# Consola_ESP32_V2.net
KiCad netlist of a schematic drawn in Altium Designer
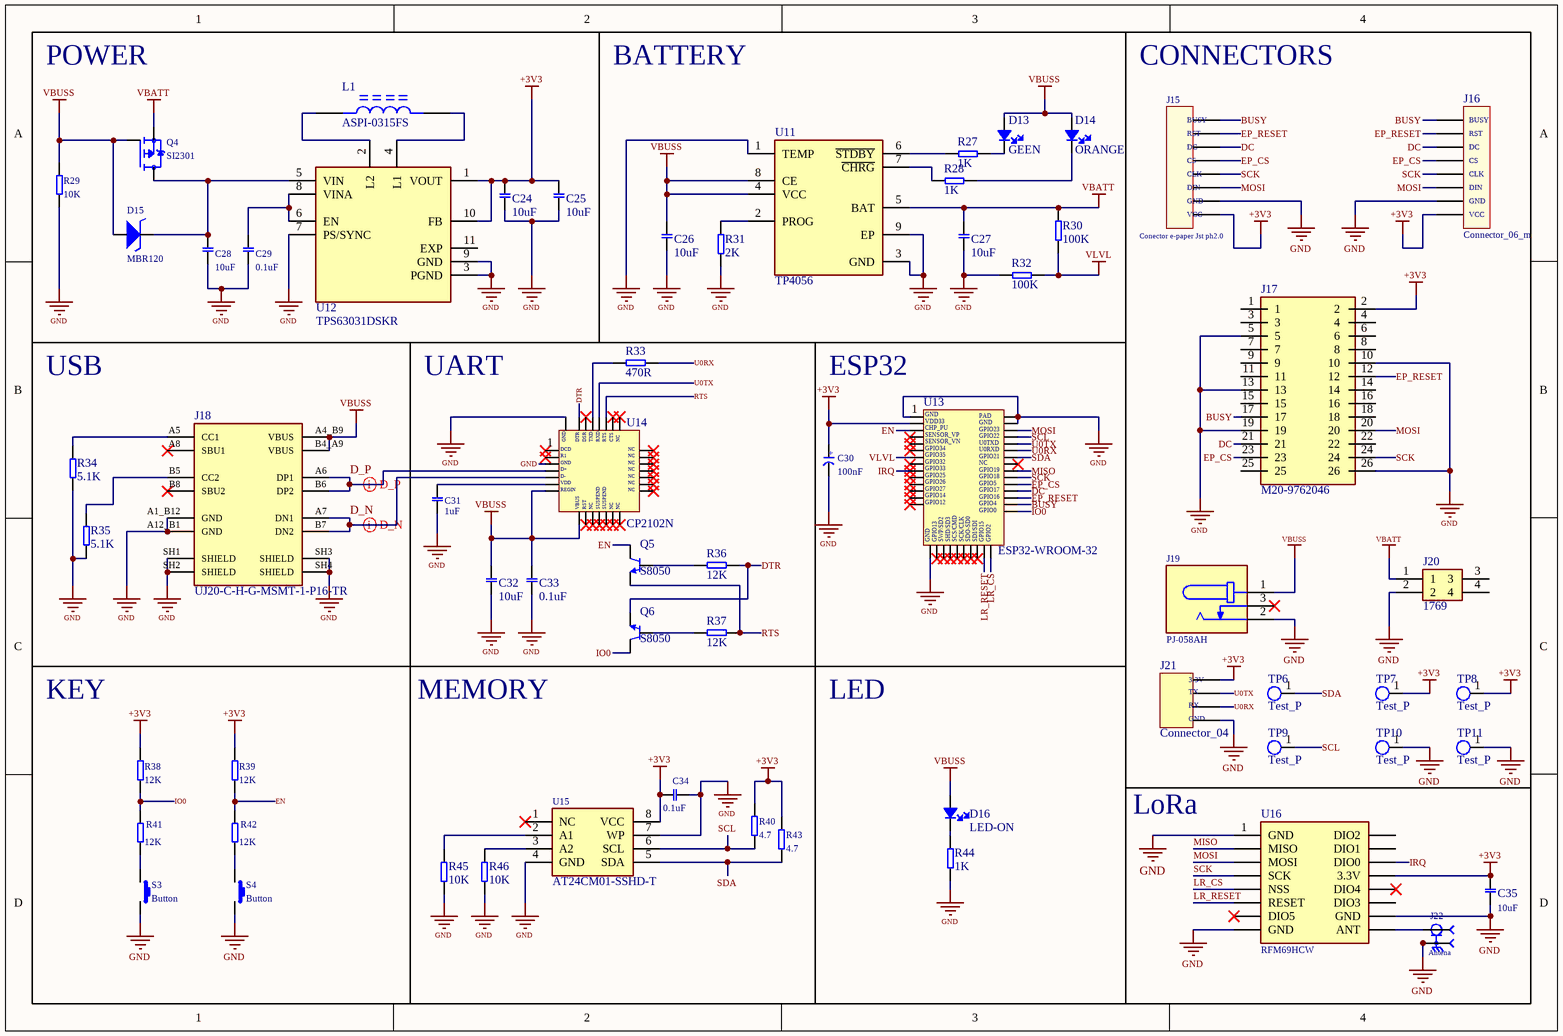
[diagram p0: Consola_ESP32_V2.SchDoc]

(export (version "E")
  (design (tool "Eeschema 10.0.6"))
  (components
    (comp (ref "C24")
      (value "10uF")
      (footprint "CAPCP1608_0603")
      (description "Capacitor_10uF_0603")
      (libsource (lib "Estacion_Meteorologica_Final") (part "C0603X100J1GACAUTO"))
    )
    (comp (ref "C25")
      (value "10uF")
      (footprint "CAPCP1608_0603")
      (description "Capacitor_10uF_0603")
      (libsource (lib "Estacion_Meteorologica_Final") (part "C0603X100J1GACAUTO"))
    )
    (comp (ref "C26")
      (value "10uF")
      (footprint "CAPCP1608_0603")
      (description "Capacitor_10uF_0603")
      (libsource (lib "Estacion_Meteorologica_Final") (part "C0603X100J1GACAUTO"))
    )
    (comp (ref "C27")
      (value "10uF")
      (footprint "CAPCP1608_0603")
      (description "Capacitor_10uF_0603")
      (libsource (lib "Estacion_Meteorologica_Final") (part "C0603X100J1GACAUTO"))
    )
    (comp (ref "C28")
      (value "10uF")
      (footprint "CAPCP1608_0603")
      (description "Capacitor_10uF_0603")
      (libsource (lib "Estacion_Meteorologica_Final") (part "C0603X100J1GACAUTO"))
    )
    (comp (ref "C29")
      (value "0.1uF")
      (footprint "CAPCP1608_0603")
      (description "Capacitor_0.1uF_0603")
      (libsource (lib "Estacion_Meteorologica_Final") (part "06035C104K4T4A"))
    )
    (comp (ref "C30")
      (value "100nF")
      (footprint "CAPC_1206")
      (description "Capacitor_100uF_1206")
      (libsource (lib "Estacion_Meteorologica_Final") (part "TAJD107K016RNJ"))
    )
    (comp (ref "C31")
      (value "1uF")
      (footprint "CAPCP1608_0603")
      (description "Capacitor_1uF_0603")
      (libsource (lib "Estacion_Meteorologica_Final") (part "C0603X105J4RACTU"))
    )
    (comp (ref "C32")
      (value "10uF")
      (footprint "CAPCP1608_0603")
      (description "Capacitor_10uF_0603")
      (libsource (lib "Estacion_Meteorologica_Final") (part "C0603X100J1GACAUTO"))
    )
    (comp (ref "C33")
      (value "0.1uF")
      (footprint "CAPCP1608_0603")
      (description "Capacitor_0.1uF_0603")
      (libsource (lib "Estacion_Meteorologica_Final") (part "06035C104K4T4A"))
    )
    (comp (ref "C34")
      (value "0.1uF")
      (footprint "CAPCP1608_0603")
      (description "Capacitor_0.1uF_0603")
      (libsource (lib "Estacion_Meteorologica_Final") (part "06035C104K4T4A"))
    )
    (comp (ref "C35")
      (value "10uF")
      (footprint "CAPCP1608_0603")
      (description "Capacitor_10uF_0603")
      (libsource (lib "Estacion_Meteorologica_Final") (part "C0603X100J1GACAUTO"))
    )
    (comp (ref "D13")
      (value "GEEN")
      (footprint "DIODO_0603")
      (description "LED_VERDE_0603")
      (libsource (lib "Estacion_Meteorologica_Final") (part "SMLD12EN1WT86"))
    )
    (comp (ref "D14")
      (value "ORANGE")
      (footprint "DIODO_0603")
      (description "LED_NARANJA_0603")
      (libsource (lib "Estacion_Meteorologica_Final") (part "SML-D12D1WT86"))
    )
    (comp (ref "D15")
      (value "MBR120")
      (footprint "SODFL3616X98N")
      (description "Diodo_Zenner_Sod-123FL-2")
      (libsource (lib "Estacion_Meteorologica_Final") (part "MBR120ESFT3G"))
    )
    (comp (ref "D16")
      (value "LED-ON")
      (footprint "DIODO_0603")
      (description "LED_VERDE_0603")
      (libsource (lib "Estacion_Meteorologica_Final") (part "SMLD12EN1WT86"))
    )
    (comp (ref "J15")
      (value "Conector e-paper Jst ph2.0")
      (footprint "CONN_S8B-PH-SM4-TB_JST")
      (description "Connector e-paper")
      (libsource (lib "Estacion_Meteorologica_Final") (part "S8B-PH-SM4-TBLFSN"))
    )
    (comp (ref "J16")
      (value "Connector_06_m")
      (footprint "HDR1X8")
      (libsource (lib "Estacion_Meteorologica_Final") (part "Connector_08_m"))
    )
    (comp (ref "J17")
      (value "M20-9762046")
      (footprint "HARWIN_M20-9762046")
      (description "2X20 - 2.54mm")
      (libsource (lib "Estacion_Meteorologica_Final") (part "M20-9762046"))
    )
    (comp (ref "J18")
      (value "UJ20-C-H-G-MSMT-1-P16-TR")
      (footprint "uJ20-C-H-G-MSMT-1-P16-TR")
      (description "Conector usb c")
      (libsource (lib "Estacion_Meteorologica_Final") (part "UJ20-C-H-G-MSMT-1-P16-TR"))
    )
    (comp (ref "J19")
      (value "PJ-058AH")
      (footprint "CUI_PJ-058AH")
      (description "2.0 x 5.7 mm, 5.0 A, Horizontal, Through Hole, Locking Type, Dc Power Jack Connector")
      (fields (field (name "MF") "CUI Devices"))
      (libsource (lib "Estacion_Meteorologica_Final") (part "PJ-058AH"))
    )
    (comp (ref "J20")
      (value "1769")
      (footprint "1769_Conector_Bateria")
      (description "Adafruit Accessories JST-PH 2-pin SMT Right Angle Connect")
      (fields (field (name "MOUSER PART NUMBER") "485-1769"))
      (libsource (lib "Estacion_Meteorologica_Final") (part "1769"))
    )
    (comp (ref "J21")
      (value "Connector_04")
      (footprint "HDR1X4")
      (libsource (lib "Estacion_Meteorologica_Final") (part "Connector_04_uart"))
    )
    (comp (ref "J22")
      (value "Antena")
      (footprint "SAMTEC_RSP-122811-01")
      (description "U.FL (UMCC), IPEX MHF1 Connector Receptacle, Male Pin 50Ohm Surface Mount Solder")
      (fields (field (name "MP") "RSP-122811-01"))
      (libsource (lib "Estacion_Meteorologica_Final") (part "RSP-122811-01"))
    )
    (comp (ref "L1")
      (value "ASPI-0315FS")
      (footprint "IND_ASPI-0315FS-1R0N-T2")
      (fields (field (name "MP") "ASPI-0315FS-1R0N-T2"))
      (libsource (lib "Estacion_Meteorologica_Final") (part "ASPI-0315FS-1R0N-T2"))
    )
    (comp (ref "Q4")
      (value "SI2301")
      (footprint "SOT-23")
      (description "P-Channel 20 V 3.1A (Tc) 860mW (Ta), 1.6W (Tc) Surface Mount SOT-23")
      (fields (field (name "MF") "Vishay") (field (name "MP") "SI2301CDS-T1-GE3"))
      (libsource (lib "Estacion_Meteorologica_Final") (part "SI2301CDS-T1-GE3"))
    )
    (comp (ref "Q5")
      (value "S8050")
      (footprint "SOT23_8050_JY3")
      (description "Transistor_Sot_23_j3y")
      (libsource (lib "Estacion_Meteorologica_Final") (part "ASS8050-L-HF"))
    )
    (comp (ref "Q6")
      (value "S8050")
      (footprint "SOT23_8050_JY3")
      (description "Transistor_Sot_23_j3y")
      (libsource (lib "Estacion_Meteorologica_Final") (part "ASS8050-L-HF"))
    )
    (comp (ref "R27")
      (value "1K")
      (footprint "RESC1608_0603")
      (description "Resistencia_1K_0603")
      (libsource (lib "Estacion_Meteorologica_Final") (part "RCA06031K00JNEA"))
    )
    (comp (ref "R28")
      (value "1K")
      (footprint "RESC1608_0603")
      (description "Resistencia_1K_0603")
      (libsource (lib "Estacion_Meteorologica_Final") (part "RCA06031K00JNEA"))
    )
    (comp (ref "R29")
      (value "10K")
      (footprint "RESC1608_0603")
      (description "Resistencia_10K_0603")
      (libsource (lib "Estacion_Meteorologica_Final") (part "RCA060310K0JNEA"))
    )
    (comp (ref "R30")
      (value "100K")
      (footprint "RESC1608_0603")
      (description "Resistencia_100K_0603")
      (libsource (lib "Estacion_Meteorologica_Final") (part "RCA0603100KFKEAHP"))
    )
    (comp (ref "R31")
      (value "2K")
      (footprint "RESC1608_0603")
      (description "Resistencia_2K_0603")
      (libsource (lib "Estacion_Meteorologica_Final") (part "RCA06032K00FKEA"))
    )
    (comp (ref "R32")
      (value "100K")
      (footprint "RESC1608_0603")
      (description "Resistencia_100K_0603")
      (libsource (lib "Estacion_Meteorologica_Final") (part "RCA0603100KFKEAHP"))
    )
    (comp (ref "R33")
      (value "470R")
      (footprint "RESC1608_0603")
      (description "Resistencia_470R_0603")
      (libsource (lib "Estacion_Meteorologica_Final") (part "RCA0603470RFKEA"))
    )
    (comp (ref "R34")
      (value "5.1K")
      (footprint "RESC1608_0603")
      (description "Resistencia_5.1K_0603")
      (libsource (lib "Estacion_Meteorologica_Final") (part "RCA06035K10JNEA"))
    )
    (comp (ref "R35")
      (value "5.1K")
      (footprint "RESC1608_0603")
      (description "Resistencia_5.1K_0603")
      (libsource (lib "Estacion_Meteorologica_Final") (part "RCA06035K10JNEA"))
    )
    (comp (ref "R36")
      (value "12K")
      (footprint "RESC1608_0603")
      (description "Resistencia_12KR_0603")
      (libsource (lib "Estacion_Meteorologica_Final") (part "RCA060312K0JNEA"))
    )
    (comp (ref "R37")
      (value "12K")
      (footprint "RESC1608_0603")
      (description "Resistencia_12KR_0603")
      (libsource (lib "Estacion_Meteorologica_Final") (part "RCA060312K0JNEA"))
    )
    (comp (ref "R38")
      (value "12K")
      (footprint "RESC1608_0603")
      (description "Resistencia_12KR_0603")
      (libsource (lib "Estacion_Meteorologica_Final") (part "RCA060312K0JNEA"))
    )
    (comp (ref "R39")
      (value "12K")
      (footprint "RESC1608_0603")
      (description "Resistencia_12KR_0603")
      (libsource (lib "Estacion_Meteorologica_Final") (part "RCA060312K0JNEA"))
    )
    (comp (ref "R40")
      (value "4.7")
      (footprint "RESC1608_0603")
      (description "Resistencia_4.7K_0603")
      (libsource (lib "Estacion_Meteorologica_Final") (part "RCA06034K70FKEA"))
    )
    (comp (ref "R41")
      (value "12K")
      (footprint "RESC1608_0603")
      (libsource (lib "Esp32_componentes_lib") (part "12KR_0603_25w"))
    )
    (comp (ref "R42")
      (value "12K")
      (footprint "RESC1608_0603")
      (libsource (lib "Esp32_componentes_lib") (part "12KR_0603_25w"))
    )
    (comp (ref "R43")
      (value "4.7")
      (footprint "RESC1608_0603")
      (description "Resistencia_4.7K_0603")
      (libsource (lib "Estacion_Meteorologica_Final") (part "RCA06034K70FKEA"))
    )
    (comp (ref "R44")
      (value "1K")
      (footprint "RESC1608_0603")
      (description "Resistencia_1K_0603")
      (libsource (lib "Estacion_Meteorologica_Final") (part "RCA06031K00JNEA"))
    )
    (comp (ref "R45")
      (value "10K")
      (footprint "RESC1608_0603")
      (description "Resistencia_10K_0603")
      (libsource (lib "Estacion_Meteorologica_Final") (part "RCA060310K0JNEA"))
    )
    (comp (ref "R46")
      (value "10K")
      (footprint "RESC1608_0603")
      (description "Resistencia_10K_0603")
      (libsource (lib "Estacion_Meteorologica_Final") (part "RCA060310K0JNEA"))
    )
    (comp (ref "S3")
      (value "Button")
      (footprint "Button_3_4_2")
      (description "Tactile Switch")
      (libsource (lib "Estacion_Meteorologica_Final") (part "Button"))
    )
    (comp (ref "S4")
      (value "Button")
      (footprint "Button_3_4_2")
      (description "Tactile Switch")
      (libsource (lib "Estacion_Meteorologica_Final") (part "Button"))
    )
    (comp (ref "TP6")
      (value "Test_P")
      (footprint "Test_point")
      (libsource (lib "Estacion_Meteorologica_Final") (part "Test_point"))
    )
    (comp (ref "TP7")
      (value "Test_P")
      (footprint "Test_point")
      (libsource (lib "Estacion_Meteorologica_Final") (part "Test_point"))
    )
    (comp (ref "TP8")
      (value "Test_P")
      (footprint "Test_point")
      (libsource (lib "Estacion_Meteorologica_Final") (part "Test_point"))
    )
    (comp (ref "TP9")
      (value "Test_P")
      (footprint "Test_point")
      (libsource (lib "Estacion_Meteorologica_Final") (part "Test_point"))
    )
    (comp (ref "TP10")
      (value "Test_P")
      (footprint "Test_point")
      (libsource (lib "Estacion_Meteorologica_Final") (part "Test_point"))
    )
    (comp (ref "TP11")
      (value "Test_P")
      (footprint "Test_point")
      (libsource (lib "Estacion_Meteorologica_Final") (part "Test_point"))
    )
    (comp (ref "U11")
      (value "TP4056")
      (footprint "SOP127P600X175-9N")
      (description "Linear Li-Ion charger IC, 4.2V CC/CV, up to 1A, auto-recharge, thermal regulation.")
      (fields (field (name "MF") "NanJing Top Power ASIC Corp."))
      (libsource (lib "Estacion_Meteorologica_Final") (part "TP4056"))
    )
    (comp (ref "U12")
      (value "TPS63031DSKR")
      (footprint "SON50P250X250X80-11N")
      (description "High Efficient Single Inductor Buck-Boost Converter with 1-A Switches")
      (libsource (lib "Estacion_Meteorologica_Final") (part "TPS63031DSKR"))
    )
    (comp (ref "U13")
      (value "ESP32-WROOM-32")
      (footprint "ESP32")
      (description "ESP-32_48Pines")
      (libsource (lib "Estacion_Meteorologica_Final") (part "ESP32-WROOM-32"))
    )
    (comp (ref "U14")
      (value "CP2102N")
      (footprint "QFN_CP2102")
      (description "Conversor USB a UART de Silicon Labs CP2102")
      (libsource (lib "Estacion_Meteorologica_Final") (part "CP2102N-A02-GQFN28R"))
    )
    (comp (ref "U15")
      (value "AT24CM01-SSHD-T")
      (footprint "SOIC-8N")
      (description "EEPROM SERIAL EEPROM, 1M 2-WIR-8 SOIC")
      (fields (field (name "MOUSER PART NUMBER") "556-AT24CM01-SSHD-T"))
      (libsource (lib "Estacion_Meteorologica_Final") (part "AT24CM01-SSHD-T"))
    )
    (comp (ref "U16")
      (value "RFM69HCW")
      (footprint "COM-13909")
      (description "Rfm69hcw Wireless Transceiver 91")
      (fields (field (name "MP") "COM-13909"))
      (libsource (lib "Estacion_Meteorologica_Final") (part "COM-13909"))
    )
  )
  (nets
    (net (code "1") (name "+3V3") (class "Default")
      (node (ref "C24") (pin "2") (pinfunction "2_2") (pintype "passive"))
      (node (ref "C25") (pin "2") (pinfunction "2_2") (pintype "passive"))
      (node (ref "C30") (pin "2") (pinfunction "2_2") (pintype "passive"))
      (node (ref "C34") (pin "1") (pinfunction "1_1") (pintype "passive"))
      (node (ref "C35") (pin "2") (pinfunction "2_2") (pintype "passive"))
      (node (ref "J15") (pin "8") (pinfunction "8_8") (pintype "passive"))
      (node (ref "J16") (pin "8") (pinfunction "8_8") (pintype "passive"))
      (node (ref "J17") (pin "2") (pinfunction "2_2") (pintype "passive"))
      (node (ref "J21") (pin "1") (pinfunction "1_1") (pintype "passive"))
      (node (ref "R38") (pin "2") (pinfunction "2_2") (pintype "passive"))
      (node (ref "R39") (pin "2") (pinfunction "2_2") (pintype "passive"))
      (node (ref "R40") (pin "2") (pinfunction "2_2") (pintype "passive"))
      (node (ref "R43") (pin "1") (pinfunction "1_1") (pintype "passive"))
      (node (ref "TP7") (pin "1") (pinfunction "1_1") (pintype "passive"))
      (node (ref "TP8") (pin "1") (pinfunction "1_1") (pintype "passive"))
      (node (ref "U12") (pin "1") (pinfunction "VOUT_1") (pintype "passive"))
      (node (ref "U12") (pin "10") (pinfunction "FB_10") (pintype "passive"))
      (node (ref "U13") (pin "2") (pinfunction "2_2") (pintype "passive"))
      (node (ref "U15") (pin "8") (pinfunction "VCC_8") (pintype "passive"))
      (node (ref "U16") (pin "13") (pinfunction "3.3V_13") (pintype "passive"))
    )
    (net (code "2") (name "/BUSY") (class "Default")
      (node (ref "J15") (pin "1") (pinfunction "1_1") (pintype "passive"))
      (node (ref "J16") (pin "1") (pinfunction "1_1") (pintype "passive"))
      (node (ref "J17") (pin "17") (pinfunction "17_17") (pintype "passive"))
      (node (ref "U13") (pin "26") (pinfunction "26_26") (pintype "passive"))
    )
    (net (code "3") (name "/DC") (class "Default")
      (node (ref "J15") (pin "3") (pinfunction "3_3") (pintype "passive"))
      (node (ref "J16") (pin "3") (pinfunction "3_3") (pintype "passive"))
      (node (ref "J17") (pin "21") (pinfunction "21_21") (pintype "passive"))
      (node (ref "U13") (pin "28") (pinfunction "28_28") (pintype "passive"))
    )
    (net (code "4") (name "/DTR") (class "Default")
      (node (ref "Q6") (pin "3") (pinfunction "3_3") (pintype "passive"))
      (node (ref "R36") (pin "2") (pinfunction "2_2") (pintype "passive"))
      (node (ref "U14") (pin "28") (pinfunction "28_28") (pintype "passive"))
    )
    (net (code "5") (name "/D_N") (class "Default")
      (node (ref "J18") (pin "A7") (pinfunction "DN1_A7") (pintype "passive"))
      (node (ref "J18") (pin "B7") (pinfunction "DN2_B7") (pintype "passive"))
      (node (ref "U14") (pin "5") (pinfunction "5_5") (pintype "passive"))
    )
    (net (code "6") (name "/D_P") (class "Default")
      (node (ref "J18") (pin "A6") (pinfunction "DP1_A6") (pintype "passive"))
      (node (ref "J18") (pin "B6") (pinfunction "DP2_B6") (pintype "passive"))
      (node (ref "U14") (pin "4") (pinfunction "4_4") (pintype "passive"))
    )
    (net (code "7") (name "/EN") (class "Default")
      (node (ref "Q5") (pin "1") (pinfunction "1_1") (pintype "passive"))
      (node (ref "R39") (pin "1") (pinfunction "1_1") (pintype "passive"))
      (node (ref "R42") (pin "2") (pinfunction "2_2") (pintype "passive"))
      (node (ref "U13") (pin "3") (pinfunction "3_3") (pintype "passive"))
    )
    (net (code "8") (name "/EP_CS") (class "Default")
      (node (ref "J15") (pin "4") (pinfunction "4_4") (pintype "passive"))
      (node (ref "J16") (pin "4") (pinfunction "4_4") (pintype "passive"))
      (node (ref "J17") (pin "23") (pinfunction "23_23") (pintype "passive"))
      (node (ref "U13") (pin "29") (pinfunction "29_29") (pintype "passive"))
    )
    (net (code "9") (name "/EP_RESET") (class "Default")
      (node (ref "J15") (pin "2") (pinfunction "2_2") (pintype "passive"))
      (node (ref "J16") (pin "2") (pinfunction "2_2") (pintype "passive"))
      (node (ref "J17") (pin "12") (pinfunction "12_12") (pintype "passive"))
      (node (ref "U13") (pin "27") (pinfunction "27_27") (pintype "passive"))
    )
    (net (code "10") (name "/IO0") (class "Default")
      (node (ref "Q6") (pin "1") (pinfunction "1_1") (pintype "passive"))
      (node (ref "R38") (pin "1") (pinfunction "1_1") (pintype "passive"))
      (node (ref "R41") (pin "2") (pinfunction "2_2") (pintype "passive"))
      (node (ref "U13") (pin "25") (pinfunction "25_25") (pintype "passive"))
    )
    (net (code "11") (name "/IRQ") (class "Default")
      (node (ref "U13") (pin "9") (pinfunction "9_9") (pintype "passive"))
      (node (ref "U16") (pin "14") (pinfunction "DIO0_14") (pintype "passive"))
    )
    (net (code "12") (name "/LR_CS") (class "Default")
      (node (ref "U13") (pin "24") (pinfunction "24_24") (pintype "passive"))
      (node (ref "U16") (pin "5") (pinfunction "NSS_5") (pintype "passive"))
    )
    (net (code "13") (name "/LR_RESET") (class "Default")
      (node (ref "U13") (pin "23") (pinfunction "23_23") (pintype "passive"))
      (node (ref "U16") (pin "6") (pinfunction "RESET_6") (pintype "passive"))
    )
    (net (code "14") (name "/MISO") (class "Default")
      (node (ref "U13") (pin "31") (pinfunction "31_31") (pintype "passive"))
      (node (ref "U16") (pin "2") (pinfunction "MISO_2") (pintype "passive"))
    )
    (net (code "15") (name "/MOSI") (class "Default")
      (node (ref "J15") (pin "6") (pinfunction "6_6") (pintype "passive"))
      (node (ref "J16") (pin "6") (pinfunction "6_6") (pintype "passive"))
      (node (ref "J17") (pin "20") (pinfunction "20_20") (pintype "passive"))
      (node (ref "U13") (pin "37") (pinfunction "37_37") (pintype "passive"))
      (node (ref "U16") (pin "3") (pinfunction "MOSI_3") (pintype "passive"))
    )
    (net (code "16") (name "/RTS") (class "Default")
      (node (ref "Q5") (pin "3") (pinfunction "3_3") (pintype "passive"))
      (node (ref "R37") (pin "2") (pinfunction "2_2") (pintype "passive"))
      (node (ref "U14") (pin "24") (pinfunction "24_24") (pintype "passive"))
    )
    (net (code "17") (name "/SCK") (class "Default")
      (node (ref "J15") (pin "5") (pinfunction "5_5") (pintype "passive"))
      (node (ref "J16") (pin "5") (pinfunction "5_5") (pintype "passive"))
      (node (ref "J17") (pin "24") (pinfunction "24_24") (pintype "passive"))
      (node (ref "U13") (pin "30") (pinfunction "30_30") (pintype "passive"))
      (node (ref "U16") (pin "4") (pinfunction "SCK_4") (pintype "passive"))
    )
    (net (code "18") (name "/SCL") (class "Default")
      (node (ref "R40") (pin "1") (pinfunction "1_1") (pintype "passive"))
      (node (ref "TP9") (pin "1") (pinfunction "1_1") (pintype "passive"))
      (node (ref "U13") (pin "36") (pinfunction "36_36") (pintype "passive"))
      (node (ref "U15") (pin "6") (pinfunction "SCL_6") (pintype "passive"))
    )
    (net (code "19") (name "/SDA") (class "Default")
      (node (ref "R43") (pin "2") (pinfunction "2_2") (pintype "passive"))
      (node (ref "TP6") (pin "1") (pinfunction "1_1") (pintype "passive"))
      (node (ref "U13") (pin "33") (pinfunction "33_33") (pintype "passive"))
      (node (ref "U15") (pin "5") (pinfunction "SDA_5") (pintype "passive"))
    )
    (net (code "20") (name "/U0RX") (class "Default")
      (node (ref "J21") (pin "3") (pinfunction "3_3") (pintype "passive"))
      (node (ref "R33") (pin "2") (pinfunction "2_2") (pintype "passive"))
      (node (ref "U13") (pin "34") (pinfunction "34_34") (pintype "passive"))
    )
    (net (code "21") (name "/U0TX") (class "Default")
      (node (ref "J21") (pin "2") (pinfunction "2_2") (pintype "passive"))
      (node (ref "U13") (pin "35") (pinfunction "35_35") (pintype "passive"))
      (node (ref "U14") (pin "25") (pinfunction "25_25") (pintype "passive"))
    )
    (net (code "22") (name "GND") (class "Default")
      (node (ref "C24") (pin "1") (pinfunction "1_1") (pintype "passive"))
      (node (ref "C25") (pin "1") (pinfunction "1_1") (pintype "passive"))
      (node (ref "C26") (pin "1") (pinfunction "1_1") (pintype "passive"))
      (node (ref "C27") (pin "1") (pinfunction "1_1") (pintype "passive"))
      (node (ref "C28") (pin "1") (pinfunction "1_1") (pintype "passive"))
      (node (ref "C29") (pin "1") (pinfunction "1_1") (pintype "passive"))
      (node (ref "C30") (pin "1") (pinfunction "1_1") (pintype "passive"))
      (node (ref "C31") (pin "2") (pinfunction "2_2") (pintype "passive"))
      (node (ref "C32") (pin "1") (pinfunction "1_1") (pintype "passive"))
      (node (ref "C33") (pin "1") (pinfunction "1_1") (pintype "passive"))
      (node (ref "C34") (pin "2") (pinfunction "2_2") (pintype "passive"))
      (node (ref "C35") (pin "1") (pinfunction "1_1") (pintype "passive"))
      (node (ref "J15") (pin "7") (pinfunction "7_7") (pintype "passive"))
      (node (ref "J16") (pin "7") (pinfunction "7_7") (pintype "passive"))
      (node (ref "J17") (pin "10") (pinfunction "10_10") (pintype "passive"))
      (node (ref "J17") (pin "13") (pinfunction "13_13") (pintype "passive"))
      (node (ref "J17") (pin "19") (pinfunction "19_19") (pintype "passive"))
      (node (ref "J17") (pin "26") (pinfunction "26_26") (pintype "passive"))
      (node (ref "J17") (pin "5") (pinfunction "5_5") (pintype "passive"))
      (node (ref "J18") (pin "A12_B1") (pinfunction "GND_A12_B1") (pintype "passive"))
      (node (ref "J18") (pin "A1_B12") (pinfunction "GND_A1_B12") (pintype "passive"))
      (node (ref "J18") (pin "SH1") (pinfunction "SHIELD_SH1") (pintype "passive"))
      (node (ref "J18") (pin "SH2") (pinfunction "SHIELD_SH2") (pintype "passive"))
      (node (ref "J18") (pin "SH3") (pinfunction "SHIELD_SH3") (pintype "passive"))
      (node (ref "J18") (pin "SH4") (pinfunction "SHIELD_SH4") (pintype "passive"))
      (node (ref "J19") (pin "2") (pinfunction "2_2") (pintype "passive"))
      (node (ref "J20") (pin "2") (pinfunction "2_2") (pintype "passive"))
      (node (ref "J21") (pin "4") (pinfunction "4_4") (pintype "passive"))
      (node (ref "J22") (pin "G1") (pinfunction "GND_G1") (pintype "passive"))
      (node (ref "J22") (pin "G2") (pinfunction "GND_G2") (pintype "passive"))
      (node (ref "R29") (pin "1") (pinfunction "1_1") (pintype "passive"))
      (node (ref "R31") (pin "2") (pinfunction "2_2") (pintype "passive"))
      (node (ref "R32") (pin "2") (pinfunction "2_2") (pintype "passive"))
      (node (ref "R34") (pin "1") (pinfunction "1_1") (pintype "passive"))
      (node (ref "R35") (pin "1") (pinfunction "1_1") (pintype "passive"))
      (node (ref "R44") (pin "1") (pinfunction "1_1") (pintype "passive"))
      (node (ref "R45") (pin "1") (pinfunction "1_1") (pintype "passive"))
      (node (ref "R46") (pin "1") (pinfunction "1_1") (pintype "passive"))
      (node (ref "S3") (pin "2") (pinfunction "2_2") (pintype "passive"))
      (node (ref "S4") (pin "2") (pinfunction "2_2") (pintype "passive"))
      (node (ref "TP10") (pin "1") (pinfunction "1_1") (pintype "passive"))
      (node (ref "TP11") (pin "1") (pinfunction "1_1") (pintype "passive"))
      (node (ref "U11") (pin "1") (pinfunction "TEMP_1") (pintype "passive"))
      (node (ref "U11") (pin "3") (pinfunction "GND_3") (pintype "passive"))
      (node (ref "U11") (pin "9") (pinfunction "EP_9") (pintype "passive"))
      (node (ref "U12") (pin "3") (pinfunction "PGND_3") (pintype "power_in"))
      (node (ref "U12") (pin "7") (pinfunction "PS/SYNC_7") (pintype "passive"))
      (node (ref "U12") (pin "9") (pinfunction "GND_9") (pintype "power_in"))
      (node (ref "U13") (pin "1") (pinfunction "1_1") (pintype "passive"))
      (node (ref "U13") (pin "15") (pinfunction "15_15") (pintype "passive"))
      (node (ref "U13") (pin "38") (pinfunction "38_38") (pintype "passive"))
      (node (ref "U13") (pin "39") (pinfunction "39_39") (pintype "passive"))
      (node (ref "U14") (pin "29") (pinfunction "29_29") (pintype "passive"))
      (node (ref "U14") (pin "3") (pinfunction "3_3") (pintype "passive"))
      (node (ref "U15") (pin "4") (pinfunction "GND_4") (pintype "passive"))
      (node (ref "U15") (pin "7") (pinfunction "WP_7") (pintype "passive"))
      (node (ref "U16") (pin "1") (pinfunction "GND_1") (pintype "passive"))
      (node (ref "U16") (pin "10") (pinfunction "GND_10") (pintype "passive"))
      (node (ref "U16") (pin "8") (pinfunction "GND_8") (pintype "passive"))
    )
    (net (code "23") (name "Net-(C31-Pad1)") (class "Default")
      (node (ref "C31") (pin "1") (pinfunction "1_1") (pintype "passive"))
      (node (ref "U14") (pin "6") (pinfunction "6_6") (pintype "passive"))
    )
    (net (code "24") (name "Net-(D13-Pad2)") (class "Default")
      (node (ref "D13") (pin "2") (pinfunction "2_2") (pintype "passive"))
      (node (ref "R27") (pin "1") (pinfunction "1_1") (pintype "passive"))
    )
    (net (code "25") (name "Net-(D14-Pad2)") (class "Default")
      (node (ref "D14") (pin "2") (pinfunction "2_2") (pintype "passive"))
      (node (ref "R28") (pin "1") (pinfunction "1_1") (pintype "passive"))
    )
    (net (code "26") (name "Net-(D16-Pad2)") (class "Default")
      (node (ref "D16") (pin "2") (pinfunction "2_2") (pintype "passive"))
      (node (ref "R44") (pin "2") (pinfunction "2_2") (pintype "passive"))
    )
    (net (code "27") (name "Net-(J18-CC1)") (class "Default")
      (node (ref "J18") (pin "A5") (pinfunction "CC1_A5") (pintype "passive"))
      (node (ref "R34") (pin "2") (pinfunction "2_2") (pintype "passive"))
    )
    (net (code "28") (name "Net-(J18-CC2)") (class "Default")
      (node (ref "J18") (pin "B5") (pinfunction "CC2_B5") (pintype "passive"))
      (node (ref "R35") (pin "2") (pinfunction "2_2") (pintype "passive"))
    )
    (net (code "29") (name "Net-(Q4-D)") (class "Default")
      (node (ref "C28") (pin "2") (pinfunction "2_2") (pintype "passive"))
      (node (ref "D15") (pin "2") (pinfunction "2_2") (pintype "passive"))
      (node (ref "Q4") (pin "3") (pinfunction "D_3") (pintype "passive"))
      (node (ref "U12") (pin "5") (pinfunction "VIN_5") (pintype "passive"))
    )
    (net (code "30") (name "Net-(Q5-Pad2)") (class "Default")
      (node (ref "Q5") (pin "2") (pinfunction "2_2") (pintype "passive"))
      (node (ref "R36") (pin "1") (pinfunction "1_1") (pintype "passive"))
    )
    (net (code "31") (name "Net-(Q6-Pad2)") (class "Default")
      (node (ref "Q6") (pin "2") (pinfunction "2_2") (pintype "passive"))
      (node (ref "R37") (pin "1") (pinfunction "1_1") (pintype "passive"))
    )
    (net (code "32") (name "Net-(R33-Pad1)") (class "Default")
      (node (ref "R33") (pin "1") (pinfunction "1_1") (pintype "passive"))
      (node (ref "U14") (pin "26") (pinfunction "26_26") (pintype "passive"))
    )
    (net (code "33") (name "Net-(R41-Pad1)") (class "Default")
      (node (ref "R41") (pin "1") (pinfunction "1_1") (pintype "passive"))
      (node (ref "S3") (pin "1") (pinfunction "1_1") (pintype "passive"))
    )
    (net (code "34") (name "Net-(R42-Pad1)") (class "Default")
      (node (ref "R42") (pin "1") (pinfunction "1_1") (pintype "passive"))
      (node (ref "S4") (pin "1") (pinfunction "1_1") (pintype "passive"))
    )
    (net (code "35") (name "Net-(U11-PROG)") (class "Default")
      (node (ref "R31") (pin "1") (pinfunction "1_1") (pintype "passive"))
      (node (ref "U11") (pin "2") (pinfunction "PROG_2") (pintype "passive"))
    )
    (net (code "36") (name "Net-(U11-~{CHRG})") (class "Default")
      (node (ref "R28") (pin "2") (pinfunction "2_2") (pintype "passive"))
      (node (ref "U11") (pin "7") (pinfunction "~{CHRG}_7") (pintype "passive"))
    )
    (net (code "37") (name "Net-(U11-~{STDBY})") (class "Default")
      (node (ref "R27") (pin "2") (pinfunction "2_2") (pintype "passive"))
      (node (ref "U11") (pin "6") (pinfunction "~{STDBY}_6") (pintype "passive"))
    )
    (net (code "38") (name "Net-(U12-EN)") (class "Default")
      (node (ref "C29") (pin "2") (pinfunction "2_2") (pintype "passive"))
      (node (ref "U12") (pin "6") (pinfunction "EN_6") (pintype "passive"))
      (node (ref "U12") (pin "8") (pinfunction "VINA_8") (pintype "passive"))
    )
    (net (code "39") (name "Net-(U12-L1)") (class "Default")
      (node (ref "L1") (pin "2") (pinfunction "2_2") (pintype "passive"))
      (node (ref "U12") (pin "4") (pinfunction "L1_4") (pintype "passive"))
    )
    (net (code "40") (name "Net-(U12-L2)") (class "Default")
      (node (ref "L1") (pin "1") (pinfunction "1_1") (pintype "passive"))
      (node (ref "U12") (pin "2") (pinfunction "L2_2") (pintype "passive"))
    )
    (net (code "41") (name "Net-(U15-A1)") (class "Default")
      (node (ref "R45") (pin "2") (pinfunction "2_2") (pintype "passive"))
      (node (ref "U15") (pin "2") (pinfunction "A1_2") (pintype "passive"))
    )
    (net (code "42") (name "Net-(U15-A2)") (class "Default")
      (node (ref "R46") (pin "2") (pinfunction "2_2") (pintype "passive"))
      (node (ref "U15") (pin "3") (pinfunction "A2_3") (pintype "passive"))
    )
    (net (code "43") (name "Net-(U16-ANT)") (class "Default")
      (node (ref "J22") (pin "1") (pinfunction "1_1") (pintype "passive"))
      (node (ref "U16") (pin "9") (pinfunction "ANT_9") (pintype "passive"))
    )
    (net (code "44") (name "VBATT") (class "Default")
      (node (ref "C27") (pin "2") (pinfunction "2_2") (pintype "passive"))
      (node (ref "J20") (pin "1") (pinfunction "1_1") (pintype "passive"))
      (node (ref "Q4") (pin "2") (pinfunction "S_2") (pintype "passive"))
      (node (ref "R30") (pin "2") (pinfunction "2_2") (pintype "passive"))
      (node (ref "U11") (pin "5") (pinfunction "BAT_5") (pintype "passive"))
    )
    (net (code "45") (name "VBUSS") (class "Default")
      (node (ref "C26") (pin "2") (pinfunction "2_2") (pintype "passive"))
      (node (ref "C32") (pin "2") (pinfunction "2_2") (pintype "passive"))
      (node (ref "C33") (pin "2") (pinfunction "2_2") (pintype "passive"))
      (node (ref "D13") (pin "1") (pinfunction "1_1") (pintype "passive"))
      (node (ref "D14") (pin "1") (pinfunction "1_1") (pintype "passive"))
      (node (ref "D15") (pin "1") (pinfunction "1_1") (pintype "passive"))
      (node (ref "D16") (pin "1") (pinfunction "1_1") (pintype "passive"))
      (node (ref "J18") (pin "A4_B9") (pinfunction "VBUS_A4_B9") (pintype "passive"))
      (node (ref "J18") (pin "B4_A9") (pinfunction "VBUS_B4_A9") (pintype "passive"))
      (node (ref "J19") (pin "1") (pinfunction "1_1") (pintype "passive"))
      (node (ref "Q4") (pin "1") (pinfunction "G_1") (pintype "passive"))
      (node (ref "R29") (pin "2") (pinfunction "2_2") (pintype "passive"))
      (node (ref "U11") (pin "4") (pinfunction "VCC_4") (pintype "passive"))
      (node (ref "U11") (pin "8") (pinfunction "CE_8") (pintype "passive"))
      (node (ref "U14") (pin "7") (pinfunction "7_7") (pintype "passive"))
      (node (ref "U14") (pin "8") (pinfunction "8_8") (pintype "passive"))
    )
    (net (code "46") (name "VLVL") (class "Default")
      (node (ref "R30") (pin "1") (pinfunction "1_1") (pintype "passive"))
      (node (ref "R32") (pin "1") (pinfunction "1_1") (pintype "passive"))
      (node (ref "U13") (pin "7") (pinfunction "7_7") (pintype "passive"))
    )
    (net (code "47") (name "unconnected-(J17-Pad1)") (class "Default")
      (node (ref "J17") (pin "1") (pinfunction "1_1") (pintype "passive"))
    )
    (net (code "48") (name "unconnected-(J17-Pad3)") (class "Default")
      (node (ref "J17") (pin "3") (pinfunction "3_3") (pintype "passive"))
    )
    (net (code "49") (name "unconnected-(J17-Pad4)") (class "Default")
      (node (ref "J17") (pin "4") (pinfunction "4_4") (pintype "passive"))
    )
    (net (code "50") (name "unconnected-(J17-Pad6)") (class "Default")
      (node (ref "J17") (pin "6") (pinfunction "6_6") (pintype "passive"))
    )
    (net (code "51") (name "unconnected-(J17-Pad7)") (class "Default")
      (node (ref "J17") (pin "7") (pinfunction "7_7") (pintype "passive"))
    )
    (net (code "52") (name "unconnected-(J17-Pad8)") (class "Default")
      (node (ref "J17") (pin "8") (pinfunction "8_8") (pintype "passive"))
    )
    (net (code "53") (name "unconnected-(J17-Pad9)") (class "Default")
      (node (ref "J17") (pin "9") (pinfunction "9_9") (pintype "passive"))
    )
    (net (code "54") (name "unconnected-(J17-Pad11)") (class "Default")
      (node (ref "J17") (pin "11") (pinfunction "11_11") (pintype "passive"))
    )
    (net (code "55") (name "unconnected-(J17-Pad14)") (class "Default")
      (node (ref "J17") (pin "14") (pinfunction "14_14") (pintype "passive"))
    )
    (net (code "56") (name "unconnected-(J17-Pad15)") (class "Default")
      (node (ref "J17") (pin "15") (pinfunction "15_15") (pintype "passive"))
    )
    (net (code "57") (name "unconnected-(J17-Pad16)") (class "Default")
      (node (ref "J17") (pin "16") (pinfunction "16_16") (pintype "passive"))
    )
    (net (code "58") (name "unconnected-(J17-Pad18)") (class "Default")
      (node (ref "J17") (pin "18") (pinfunction "18_18") (pintype "passive"))
    )
    (net (code "59") (name "unconnected-(J17-Pad22)") (class "Default")
      (node (ref "J17") (pin "22") (pinfunction "22_22") (pintype "passive"))
    )
    (net (code "60") (name "unconnected-(J17-Pad25)") (class "Default")
      (node (ref "J17") (pin "25") (pinfunction "25_25") (pintype "passive"))
    )
    (net (code "61") (name "unconnected-(J18-SBU1-PadA8)") (class "Default")
      (node (ref "J18") (pin "A8") (pinfunction "SBU1_A8") (pintype "passive+no_connect"))
    )
    (net (code "62") (name "unconnected-(J18-SBU2-PadB8)") (class "Default")
      (node (ref "J18") (pin "B8") (pinfunction "SBU2_B8") (pintype "passive+no_connect"))
    )
    (net (code "63") (name "unconnected-(J19-Pad3)") (class "Default")
      (node (ref "J19") (pin "3") (pinfunction "3_3") (pintype "passive+no_connect"))
    )
    (net (code "64") (name "unconnected-(J20-Pad3)") (class "Default")
      (node (ref "J20") (pin "3") (pinfunction "3_3") (pintype "passive"))
    )
    (net (code "65") (name "unconnected-(J20-Pad4)") (class "Default")
      (node (ref "J20") (pin "4") (pinfunction "4_4") (pintype "passive"))
    )
    (net (code "66") (name "unconnected-(U12-EXP-Pad11)") (class "Default")
      (node (ref "U12") (pin "11") (pinfunction "EXP_11") (pintype "passive"))
    )
    (net (code "67") (name "unconnected-(U13-Pad4)") (class "Default")
      (node (ref "U13") (pin "4") (pinfunction "4_4") (pintype "passive+no_connect"))
    )
    (net (code "68") (name "unconnected-(U13-Pad5)") (class "Default")
      (node (ref "U13") (pin "5") (pinfunction "5_5") (pintype "passive+no_connect"))
    )
    (net (code "69") (name "unconnected-(U13-Pad6)") (class "Default")
      (node (ref "U13") (pin "6") (pinfunction "6_6") (pintype "passive+no_connect"))
    )
    (net (code "70") (name "unconnected-(U13-Pad8)") (class "Default")
      (node (ref "U13") (pin "8") (pinfunction "8_8") (pintype "passive+no_connect"))
    )
    (net (code "71") (name "unconnected-(U13-Pad10)") (class "Default")
      (node (ref "U13") (pin "10") (pinfunction "10_10") (pintype "passive+no_connect"))
    )
    (net (code "72") (name "unconnected-(U13-Pad11)") (class "Default")
      (node (ref "U13") (pin "11") (pinfunction "11_11") (pintype "passive+no_connect"))
    )
    (net (code "73") (name "unconnected-(U13-Pad12)") (class "Default")
      (node (ref "U13") (pin "12") (pinfunction "12_12") (pintype "passive+no_connect"))
    )
    (net (code "74") (name "unconnected-(U13-Pad13)") (class "Default")
      (node (ref "U13") (pin "13") (pinfunction "13_13") (pintype "passive+no_connect"))
    )
    (net (code "75") (name "unconnected-(U13-Pad14)") (class "Default")
      (node (ref "U13") (pin "14") (pinfunction "14_14") (pintype "passive+no_connect"))
    )
    (net (code "76") (name "unconnected-(U13-Pad16)") (class "Default")
      (node (ref "U13") (pin "16") (pinfunction "16_16") (pintype "passive+no_connect"))
    )
    (net (code "77") (name "unconnected-(U13-Pad17)") (class "Default")
      (node (ref "U13") (pin "17") (pinfunction "17_17") (pintype "passive+no_connect"))
    )
    (net (code "78") (name "unconnected-(U13-Pad18)") (class "Default")
      (node (ref "U13") (pin "18") (pinfunction "18_18") (pintype "passive+no_connect"))
    )
    (net (code "79") (name "unconnected-(U13-Pad19)") (class "Default")
      (node (ref "U13") (pin "19") (pinfunction "19_19") (pintype "passive+no_connect"))
    )
    (net (code "80") (name "unconnected-(U13-Pad20)") (class "Default")
      (node (ref "U13") (pin "20") (pinfunction "20_20") (pintype "passive+no_connect"))
    )
    (net (code "81") (name "unconnected-(U13-Pad21)") (class "Default")
      (node (ref "U13") (pin "21") (pinfunction "21_21") (pintype "passive+no_connect"))
    )
    (net (code "82") (name "unconnected-(U13-Pad22)") (class "Default")
      (node (ref "U13") (pin "22") (pinfunction "22_22") (pintype "passive+no_connect"))
    )
    (net (code "83") (name "unconnected-(U13-Pad32)") (class "Default")
      (node (ref "U13") (pin "32") (pinfunction "32_32") (pintype "passive+no_connect"))
    )
    (net (code "84") (name "unconnected-(U14-Pad1)") (class "Default")
      (node (ref "U14") (pin "1") (pinfunction "1_1") (pintype "passive+no_connect"))
    )
    (net (code "85") (name "unconnected-(U14-Pad2)") (class "Default")
      (node (ref "U14") (pin "2") (pinfunction "2_2") (pintype "passive+no_connect"))
    )
    (net (code "86") (name "unconnected-(U14-Pad9)") (class "Default")
      (node (ref "U14") (pin "9") (pinfunction "9_9") (pintype "passive+no_connect"))
    )
    (net (code "87") (name "unconnected-(U14-Pad10)") (class "Default")
      (node (ref "U14") (pin "10") (pinfunction "10_10") (pintype "passive+no_connect"))
    )
    (net (code "88") (name "unconnected-(U14-Pad11)") (class "Default")
      (node (ref "U14") (pin "11") (pinfunction "11_11") (pintype "passive+no_connect"))
    )
    (net (code "89") (name "unconnected-(U14-Pad12)") (class "Default")
      (node (ref "U14") (pin "12") (pinfunction "12_12") (pintype "passive+no_connect"))
    )
    (net (code "90") (name "unconnected-(U14-Pad13)") (class "Default")
      (node (ref "U14") (pin "13") (pinfunction "13_13") (pintype "passive+no_connect"))
    )
    (net (code "91") (name "unconnected-(U14-Pad14)") (class "Default")
      (node (ref "U14") (pin "14") (pinfunction "14_14") (pintype "passive+no_connect"))
    )
    (net (code "92") (name "unconnected-(U14-Pad15)") (class "Default")
      (node (ref "U14") (pin "15") (pinfunction "15_15") (pintype "passive+no_connect"))
    )
    (net (code "93") (name "unconnected-(U14-Pad16)") (class "Default")
      (node (ref "U14") (pin "16") (pinfunction "16_16") (pintype "passive+no_connect"))
    )
    (net (code "94") (name "unconnected-(U14-Pad17)") (class "Default")
      (node (ref "U14") (pin "17") (pinfunction "17_17") (pintype "passive+no_connect"))
    )
    (net (code "95") (name "unconnected-(U14-Pad18)") (class "Default")
      (node (ref "U14") (pin "18") (pinfunction "18_18") (pintype "passive+no_connect"))
    )
    (net (code "96") (name "unconnected-(U14-Pad19)") (class "Default")
      (node (ref "U14") (pin "19") (pinfunction "19_19") (pintype "passive+no_connect"))
    )
    (net (code "97") (name "unconnected-(U14-Pad20)") (class "Default")
      (node (ref "U14") (pin "20") (pinfunction "20_20") (pintype "passive+no_connect"))
    )
    (net (code "98") (name "unconnected-(U14-Pad21)") (class "Default")
      (node (ref "U14") (pin "21") (pinfunction "21_21") (pintype "passive+no_connect"))
    )
    (net (code "99") (name "unconnected-(U14-Pad22)") (class "Default")
      (node (ref "U14") (pin "22") (pinfunction "22_22") (pintype "passive+no_connect"))
    )
    (net (code "100") (name "unconnected-(U14-Pad23)") (class "Default")
      (node (ref "U14") (pin "23") (pinfunction "23_23") (pintype "passive+no_connect"))
    )
    (net (code "101") (name "unconnected-(U14-Pad27)") (class "Default")
      (node (ref "U14") (pin "27") (pinfunction "27_27") (pintype "passive+no_connect"))
    )
    (net (code "102") (name "unconnected-(U15-NC-Pad1)") (class "Default")
      (node (ref "U15") (pin "1") (pinfunction "NC_1") (pintype "passive+no_connect"))
    )
    (net (code "103") (name "unconnected-(U16-DIO1-Pad15)") (class "Default")
      (node (ref "U16") (pin "15") (pinfunction "DIO1_15") (pintype "passive"))
    )
    (net (code "104") (name "unconnected-(U16-DIO2-Pad16)") (class "Default")
      (node (ref "U16") (pin "16") (pinfunction "DIO2_16") (pintype "passive"))
    )
    (net (code "105") (name "unconnected-(U16-DIO3-Pad11)") (class "Default")
      (node (ref "U16") (pin "11") (pinfunction "DIO3_11") (pintype "passive"))
    )
    (net (code "106") (name "unconnected-(U16-DIO4-Pad12)") (class "Default")
      (node (ref "U16") (pin "12") (pinfunction "DIO4_12") (pintype "passive+no_connect"))
    )
    (net (code "107") (name "unconnected-(U16-DIO5-Pad7)") (class "Default")
      (node (ref "U16") (pin "7") (pinfunction "DIO5_7") (pintype "passive+no_connect"))
    )
  )
)
